# mcu_v042.net
KiCad netlist of a schematic drawn in EAGLE
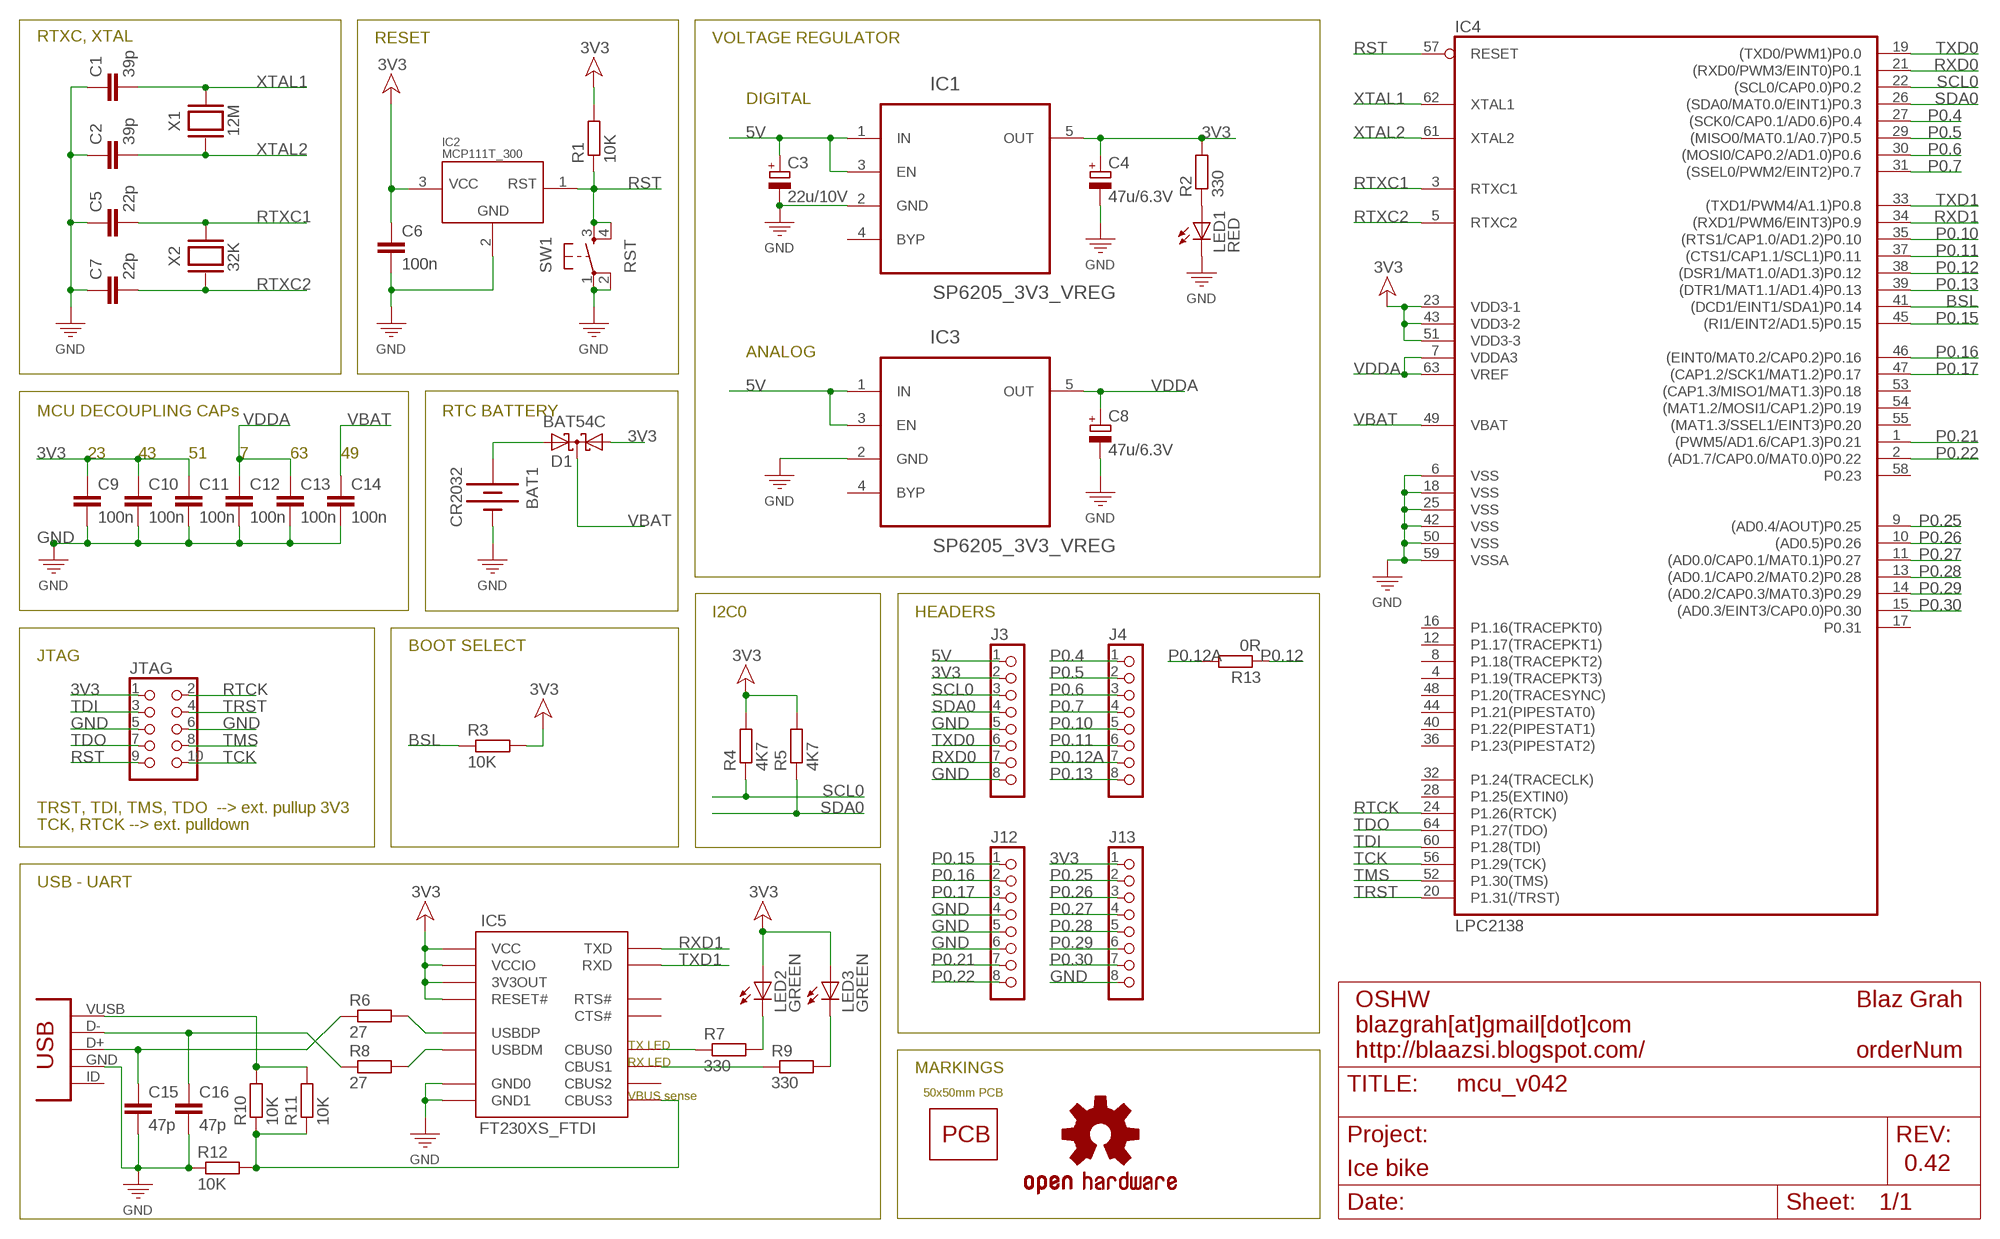
[diagram p0: schematic, sheet 1]

(export (version "E")
  (design (tool "Eeschema 10.0.6"))
  (components
    (comp (ref "BAT1")
      (value "CR2032")
      (footprint "eagle-import:BATTERY_20MM_SMD")
      (libsource (lib "eagle-import") (part "BATTERY20MM"))
    )
    (comp (ref "C1")
      (value "39p")
      (footprint "eagle-import:C0603")
      (libsource (lib "eagle-import") (part "C-EUC0603"))
    )
    (comp (ref "C2")
      (value "39p")
      (footprint "eagle-import:C0603")
      (libsource (lib "eagle-import") (part "C-EUC0603"))
    )
    (comp (ref "C3")
      (value "22u/10V")
      (footprint "eagle-import:SMC_B")
      (libsource (lib "eagle-import") (part "CAPACITOR_POL-SMC_B"))
    )
    (comp (ref "C4")
      (value "47u/6.3V")
      (footprint "eagle-import:SMC_B")
      (libsource (lib "eagle-import") (part "CAPACITOR_POL-SMC_B"))
    )
    (comp (ref "C5")
      (value "22p")
      (footprint "eagle-import:C0603")
      (libsource (lib "eagle-import") (part "C-EUC0603"))
    )
    (comp (ref "C6")
      (value "100n")
      (footprint "eagle-import:C0603")
      (libsource (lib "eagle-import") (part "C-EUC0603"))
    )
    (comp (ref "C7")
      (value "22p")
      (footprint "eagle-import:C0603")
      (libsource (lib "eagle-import") (part "C-EUC0603"))
    )
    (comp (ref "C8")
      (value "47u/6.3V")
      (footprint "eagle-import:SMC_B")
      (libsource (lib "eagle-import") (part "CAPACITOR_POL-SMC_B"))
    )
    (comp (ref "C9")
      (value "100n")
      (footprint "eagle-import:C0603")
      (libsource (lib "eagle-import") (part "C-EUC0603"))
    )
    (comp (ref "C10")
      (value "100n")
      (footprint "eagle-import:C0603")
      (libsource (lib "eagle-import") (part "C-EUC0603"))
    )
    (comp (ref "C11")
      (value "100n")
      (footprint "eagle-import:C0603")
      (libsource (lib "eagle-import") (part "C-EUC0603"))
    )
    (comp (ref "C12")
      (value "100n")
      (footprint "eagle-import:C0603")
      (libsource (lib "eagle-import") (part "C-EUC0603"))
    )
    (comp (ref "C13")
      (value "100n")
      (footprint "eagle-import:C0603")
      (libsource (lib "eagle-import") (part "C-EUC0603"))
    )
    (comp (ref "C14")
      (value "100n")
      (footprint "eagle-import:C0603")
      (libsource (lib "eagle-import") (part "C-EUC0603"))
    )
    (comp (ref "C15")
      (value "47p")
      (footprint "eagle-import:C0603")
      (libsource (lib "eagle-import") (part "C-EUC0603"))
    )
    (comp (ref "C16")
      (value "47p")
      (footprint "eagle-import:C0603")
      (libsource (lib "eagle-import") (part "C-EUC0603"))
    )
    (comp (ref "D1")
      (value "BAT54C")
      (footprint "eagle-import:SOT23")
      (libsource (lib "eagle-import") (part "BAT54C"))
    )
    (comp (ref "DOC")
      (value "FRAME_DINA4_L")
      (footprint "eagle-import:DP_LOGO")
      (fields
        (field (name "AUTHOR") "Blaz Grah")
        (field (name "LICENSE") "OSHW")
        (field (name "PROJECT") "Ice bike")
        (field (name "REV") "0.42")
        (field (name "URL1") "blazgrah[at]gmail[dot]com")
        (field (name "URL2") "http://blaazsi.blogspot.com/")
      )
      (libsource (lib "eagle-import") (part "FRAME_DINA4_L"))
    )
    (comp (ref "IC1")
      (value "SP6205_3V3_VREG")
      (footprint "eagle-import:SOT23-5")
      (libsource (lib "eagle-import") (part "SP6205_3V3_VREG"))
    )
    (comp (ref "IC2")
      (value "MCP111T_300")
      (footprint "eagle-import:SOT23")
      (libsource (lib "eagle-import") (part "MCP111T_300"))
    )
    (comp (ref "IC3")
      (value "SP6205_3V3_VREG")
      (footprint "eagle-import:SOT23-5")
      (libsource (lib "eagle-import") (part "SP6205_3V3_VREG"))
    )
    (comp (ref "IC4")
      (value "LPC2138")
      (footprint "eagle-import:LQFP64")
      (libsource (lib "eagle-import") (part "LCP2138_LQFP64"))
    )
    (comp (ref "IC5")
      (value "FT230XS_FTDI")
      (footprint "eagle-import:SSOP16")
      (libsource (lib "eagle-import") (part "FT230XS_FTDI"))
    )
    (comp (ref "J3")
      (value "CON_HEADER_1X08-PTH")
      (footprint "eagle-import:M1X8")
      (libsource (lib "eagle-import") (part "CON_HEADER_1X08-PTH"))
    )
    (comp (ref "J4")
      (value "CON_HEADER_1X08-PTH")
      (footprint "eagle-import:M1X8")
      (libsource (lib "eagle-import") (part "CON_HEADER_1X08-PTH"))
    )
    (comp (ref "J12")
      (value "CON_HEADER_1X08-PTH")
      (footprint "eagle-import:M1X8")
      (libsource (lib "eagle-import") (part "CON_HEADER_1X08-PTH"))
    )
    (comp (ref "J13")
      (value "CON_HEADER_1X08-PTH")
      (footprint "eagle-import:M1X8")
      (libsource (lib "eagle-import") (part "CON_HEADER_1X08-PTH"))
    )
    (comp (ref "JTAG")
      (value "CON_HEADER_2X05-PTH+SHROUDED_A")
      (footprint "eagle-import:PINSHRD_PTH_2X05")
      (libsource (lib "eagle-import") (part "CON_HEADER_2X05-PTH+SHROUDED_A"))
    )
    (comp (ref "LED1")
      (value "RED")
      (footprint "eagle-import:LED0805")
      (libsource (lib "eagle-import") (part "LED0805"))
    )
    (comp (ref "LED2")
      (value "GREEN")
      (footprint "eagle-import:LED0805")
      (libsource (lib "eagle-import") (part "LED0805"))
    )
    (comp (ref "LED3")
      (value "GREEN")
      (footprint "eagle-import:LED0805")
      (libsource (lib "eagle-import") (part "LED0805"))
    )
    (comp (ref "LOGO1")
      (value "OSHW-LOGOS")
      (footprint "eagle-import:OSHW-LOGO-S")
      (libsource (lib "eagle-import") (part "OSHW-LOGOS"))
    )
    (comp (ref "PCB1")
      (value "PCB")
      (footprint "eagle-import:PCB_50X50")
      (libsource (lib "eagle-import") (part "PCB"))
    )
    (comp (ref "R1")
      (value "10K")
      (footprint "eagle-import:R0603")
      (libsource (lib "eagle-import") (part "R-EU0603"))
    )
    (comp (ref "R2")
      (value "330")
      (footprint "eagle-import:R0603")
      (libsource (lib "eagle-import") (part "R-EU0603"))
    )
    (comp (ref "R3")
      (value "10K")
      (footprint "eagle-import:R0603")
      (libsource (lib "eagle-import") (part "R-EU0603"))
    )
    (comp (ref "R4")
      (value "4K7")
      (footprint "eagle-import:R0603")
      (libsource (lib "eagle-import") (part "R-EU0603"))
    )
    (comp (ref "R5")
      (value "4K7")
      (footprint "eagle-import:R0603")
      (libsource (lib "eagle-import") (part "R-EU0603"))
    )
    (comp (ref "R6")
      (value "27")
      (footprint "eagle-import:R0603")
      (libsource (lib "eagle-import") (part "R-EU0603"))
    )
    (comp (ref "R7")
      (value "330")
      (footprint "eagle-import:R0603")
      (libsource (lib "eagle-import") (part "R-EU0603"))
    )
    (comp (ref "R8")
      (value "27")
      (footprint "eagle-import:R0603")
      (libsource (lib "eagle-import") (part "R-EU0603"))
    )
    (comp (ref "R9")
      (value "330")
      (footprint "eagle-import:R0603")
      (libsource (lib "eagle-import") (part "R-EU0603"))
    )
    (comp (ref "R10")
      (value "10K")
      (footprint "eagle-import:R0603")
      (libsource (lib "eagle-import") (part "R-EU0603"))
    )
    (comp (ref "R11")
      (value "10K")
      (footprint "eagle-import:R0603")
      (libsource (lib "eagle-import") (part "R-EU0603"))
    )
    (comp (ref "R12")
      (value "10K")
      (footprint "eagle-import:R0603")
      (libsource (lib "eagle-import") (part "R-EU0603"))
    )
    (comp (ref "R13")
      (value "0R")
      (footprint "eagle-import:R0603")
      (libsource (lib "eagle-import") (part "R-EU0603"))
    )
    (comp (ref "SW1")
      (value "RST")
      (footprint "eagle-import:BUTTON_SW_4P_SMD")
      (libsource (lib "eagle-import") (part "TACTIL_BUTTON"))
    )
    (comp (ref "USB1")
      (value "CON-USB-F-MINI-B")
      (footprint "eagle-import:CONN_USB_MINI-B")
      (libsource (lib "eagle-import") (part "CON-USB-F-MINI-B"))
    )
    (comp (ref "X1")
      (value "12M")
      (footprint "eagle-import:CRYSTAL_12M_4.8X10.6MM")
      (libsource (lib "eagle-import") (part "CRYSTALSMD_4.8X10.6"))
    )
    (comp (ref "X2")
      (value "32K")
      (footprint "eagle-import:CRYSTAL_32K_SMD")
      (libsource (lib "eagle-import") (part "CRYSTALSMD_32K"))
    )
  )
  (nets
    (net (code "1") (name "/5V") (class "Default")
      (node (ref "C3") (pin "+") (pinfunction "+_+") (pintype "passive"))
      (node (ref "IC1") (pin "1") (pinfunction "IN_1") (pintype "input"))
      (node (ref "IC1") (pin "3") (pinfunction "EN_3") (pintype "input"))
      (node (ref "IC3") (pin "1") (pinfunction "IN_1") (pintype "input"))
      (node (ref "IC3") (pin "3") (pinfunction "EN_3") (pintype "input"))
      (node (ref "J3") (pin "1") (pinfunction "1_1") (pintype "passive"))
    )
    (net (code "2") (name "/BSL") (class "Default")
      (node (ref "IC4") (pin "41") (pinfunction "(DCD1/EINT1/SDA1)P0.14_41") (pintype "bidirectional"))
      (node (ref "R3") (pin "1") (pinfunction "1_1") (pintype "passive"))
    )
    (net (code "3") (name "/P0.4") (class "Default")
      (node (ref "IC4") (pin "27") (pinfunction "(SCK0/CAP0.1/AD0.6)P0.4_27") (pintype "bidirectional"))
      (node (ref "J4") (pin "1") (pinfunction "1_1") (pintype "passive"))
    )
    (net (code "4") (name "/P0.5") (class "Default")
      (node (ref "IC4") (pin "29") (pinfunction "(MISO0/MAT0.1/A0.7)P0.5_29") (pintype "bidirectional"))
      (node (ref "J4") (pin "2") (pinfunction "2_2") (pintype "passive"))
    )
    (net (code "5") (name "/P0.6") (class "Default")
      (node (ref "IC4") (pin "30") (pinfunction "(MOSI0/CAP0.2/AD1.0)P0.6_30") (pintype "bidirectional"))
      (node (ref "J4") (pin "3") (pinfunction "3_3") (pintype "passive"))
    )
    (net (code "6") (name "/P0.7") (class "Default")
      (node (ref "IC4") (pin "31") (pinfunction "(SSEL0/PWM2/EINT2)P0.7_31") (pintype "bidirectional"))
      (node (ref "J4") (pin "4") (pinfunction "4_4") (pintype "passive"))
    )
    (net (code "7") (name "/P0.10") (class "Default")
      (node (ref "IC4") (pin "35") (pinfunction "(RTS1/CAP1.0/AD1.2)P0.10_35") (pintype "bidirectional"))
      (node (ref "J4") (pin "5") (pinfunction "5_5") (pintype "passive"))
    )
    (net (code "8") (name "/P0.11") (class "Default")
      (node (ref "IC4") (pin "37") (pinfunction "(CTS1/CAP1.1/SCL1)P0.11_37") (pintype "bidirectional"))
      (node (ref "J4") (pin "6") (pinfunction "6_6") (pintype "passive"))
    )
    (net (code "9") (name "/P0.12") (class "Default")
      (node (ref "IC4") (pin "38") (pinfunction "(DSR1/MAT1.0/AD1.3)P0.12_38") (pintype "bidirectional"))
      (node (ref "R13") (pin "1") (pinfunction "1_1") (pintype "passive"))
    )
    (net (code "10") (name "/P0.12A") (class "Default")
      (node (ref "J4") (pin "7") (pinfunction "7_7") (pintype "passive"))
      (node (ref "R13") (pin "2") (pinfunction "2_2") (pintype "passive"))
    )
    (net (code "11") (name "/P0.13") (class "Default")
      (node (ref "IC4") (pin "39") (pinfunction "(DTR1/MAT1.1/AD1.4)P0.13_39") (pintype "bidirectional"))
      (node (ref "J4") (pin "8") (pinfunction "8_8") (pintype "passive"))
    )
    (net (code "12") (name "/P0.15") (class "Default")
      (node (ref "IC4") (pin "45") (pinfunction "(RI1/EINT2/AD1.5)P0.15_45") (pintype "bidirectional"))
      (node (ref "J12") (pin "1") (pinfunction "1_1") (pintype "passive"))
    )
    (net (code "13") (name "/P0.16") (class "Default")
      (node (ref "IC4") (pin "46") (pinfunction "(EINT0/MAT0.2/CAP0.2)P0.16_46") (pintype "bidirectional"))
      (node (ref "J12") (pin "2") (pinfunction "2_2") (pintype "passive"))
    )
    (net (code "14") (name "/P0.17") (class "Default")
      (node (ref "IC4") (pin "47") (pinfunction "(CAP1.2/SCK1/MAT1.2)P0.17_47") (pintype "bidirectional"))
      (node (ref "J12") (pin "3") (pinfunction "3_3") (pintype "passive"))
    )
    (net (code "15") (name "/P0.21") (class "Default")
      (node (ref "IC4") (pin "1") (pinfunction "(PWM5/AD1.6/CAP1.3)P0.21_1") (pintype "bidirectional"))
      (node (ref "J12") (pin "7") (pinfunction "7_7") (pintype "passive"))
    )
    (net (code "16") (name "/P0.22") (class "Default")
      (node (ref "IC4") (pin "2") (pinfunction "(AD1.7/CAP0.0/MAT0.0)P0.22_2") (pintype "bidirectional"))
      (node (ref "J12") (pin "8") (pinfunction "8_8") (pintype "passive"))
    )
    (net (code "17") (name "/P0.25") (class "Default")
      (node (ref "IC4") (pin "9") (pinfunction "(AD0.4/AOUT)P0.25_9") (pintype "bidirectional"))
      (node (ref "J13") (pin "2") (pinfunction "2_2") (pintype "passive"))
    )
    (net (code "18") (name "/P0.26") (class "Default")
      (node (ref "IC4") (pin "10") (pinfunction "(AD0.5)P0.26_10") (pintype "bidirectional"))
      (node (ref "J13") (pin "3") (pinfunction "3_3") (pintype "passive"))
    )
    (net (code "19") (name "/P0.27") (class "Default")
      (node (ref "IC4") (pin "11") (pinfunction "(AD0.0/CAP0.1/MAT0.1)P0.27_11") (pintype "bidirectional"))
      (node (ref "J13") (pin "4") (pinfunction "4_4") (pintype "passive"))
    )
    (net (code "20") (name "/P0.28") (class "Default")
      (node (ref "IC4") (pin "13") (pinfunction "(AD0.1/CAP0.2/MAT0.2)P0.28_13") (pintype "bidirectional"))
      (node (ref "J13") (pin "5") (pinfunction "5_5") (pintype "passive"))
    )
    (net (code "21") (name "/P0.29") (class "Default")
      (node (ref "IC4") (pin "14") (pinfunction "(AD0.2/CAP0.3/MAT0.3)P0.29_14") (pintype "bidirectional"))
      (node (ref "J13") (pin "6") (pinfunction "6_6") (pintype "passive"))
    )
    (net (code "22") (name "/P0.30") (class "Default")
      (node (ref "IC4") (pin "15") (pinfunction "(AD0.3/EINT3/CAP0.0)P0.30_15") (pintype "bidirectional"))
      (node (ref "J13") (pin "7") (pinfunction "7_7") (pintype "passive"))
    )
    (net (code "23") (name "/RST") (class "Default")
      (node (ref "IC2") (pin "1") (pinfunction "RST_1") (pintype "output"))
      (node (ref "IC4") (pin "57") (pinfunction "RESET_57") (pintype "input"))
      (node (ref "JTAG") (pin "9") (pinfunction "9_9") (pintype "passive"))
      (node (ref "R1") (pin "1") (pinfunction "1_1") (pintype "passive"))
      (node (ref "SW1") (pin "3") (pinfunction "3_3") (pintype "passive"))
      (node (ref "SW1") (pin "4") (pinfunction "4_4") (pintype "passive"))
    )
    (net (code "24") (name "/RTCK") (class "Default")
      (node (ref "IC4") (pin "24") (pinfunction "P1.26(RTCK)_24") (pintype "bidirectional"))
      (node (ref "JTAG") (pin "2") (pinfunction "2_2") (pintype "passive"))
    )
    (net (code "25") (name "/RTXC1") (class "Default")
      (node (ref "C5") (pin "2") (pinfunction "2_2") (pintype "passive"))
      (node (ref "IC4") (pin "3") (pinfunction "RTXC1_3") (pintype "input"))
      (node (ref "X2") (pin "X2") (pinfunction "2_X2") (pintype "passive"))
    )
    (net (code "26") (name "/RTXC2") (class "Default")
      (node (ref "C7") (pin "2") (pinfunction "2_2") (pintype "passive"))
      (node (ref "IC4") (pin "5") (pinfunction "RTXC2_5") (pintype "output"))
      (node (ref "X2") (pin "X1") (pinfunction "1_X1") (pintype "passive"))
    )
    (net (code "27") (name "/RXD0") (class "Default")
      (node (ref "IC4") (pin "21") (pinfunction "(RXD0/PWM3/EINT0)P0.1_21") (pintype "bidirectional"))
      (node (ref "J3") (pin "7") (pinfunction "7_7") (pintype "passive"))
    )
    (net (code "28") (name "/RXD1") (class "Default")
      (node (ref "IC4") (pin "34") (pinfunction "(RXD1/PWM6/EINT3)P0.9_34") (pintype "bidirectional"))
      (node (ref "IC5") (pin "P$1") (pinfunction "TXD_P$1") (pintype "bidirectional"))
    )
    (net (code "29") (name "/SCL0") (class "Default")
      (node (ref "IC4") (pin "22") (pinfunction "(SCL0/CAP0.0)P0.2_22") (pintype "bidirectional"))
      (node (ref "J3") (pin "3") (pinfunction "3_3") (pintype "passive"))
      (node (ref "R4") (pin "1") (pinfunction "1_1") (pintype "passive"))
    )
    (net (code "30") (name "/SDA0") (class "Default")
      (node (ref "IC4") (pin "26") (pinfunction "(SDA0/MAT0.0/EINT1)P0.3_26") (pintype "bidirectional"))
      (node (ref "J3") (pin "4") (pinfunction "4_4") (pintype "passive"))
      (node (ref "R5") (pin "1") (pinfunction "1_1") (pintype "passive"))
    )
    (net (code "31") (name "/TCK") (class "Default")
      (node (ref "IC4") (pin "56") (pinfunction "P1.29(TCK)_56") (pintype "bidirectional"))
      (node (ref "JTAG") (pin "10") (pinfunction "10_10") (pintype "passive"))
    )
    (net (code "32") (name "/TDI") (class "Default")
      (node (ref "IC4") (pin "60") (pinfunction "P1.28(TDI)_60") (pintype "bidirectional"))
      (node (ref "JTAG") (pin "3") (pinfunction "3_3") (pintype "passive"))
    )
    (net (code "33") (name "/TDO") (class "Default")
      (node (ref "IC4") (pin "64") (pinfunction "P1.27(TDO)_64") (pintype "bidirectional"))
      (node (ref "JTAG") (pin "7") (pinfunction "7_7") (pintype "passive"))
    )
    (net (code "34") (name "/TMS") (class "Default")
      (node (ref "IC4") (pin "52") (pinfunction "P1.30(TMS)_52") (pintype "bidirectional"))
      (node (ref "JTAG") (pin "8") (pinfunction "8_8") (pintype "passive"))
    )
    (net (code "35") (name "/TRST") (class "Default")
      (node (ref "IC4") (pin "20") (pinfunction "P1.31(/TRST)_20") (pintype "bidirectional"))
      (node (ref "JTAG") (pin "4") (pinfunction "4_4") (pintype "passive"))
    )
    (net (code "36") (name "/TXD0") (class "Default")
      (node (ref "IC4") (pin "19") (pinfunction "(TXD0/PWM1)P0.0_19") (pintype "bidirectional"))
      (node (ref "J3") (pin "6") (pinfunction "6_6") (pintype "passive"))
    )
    (net (code "37") (name "/TXD1") (class "Default")
      (node (ref "IC4") (pin "33") (pinfunction "(TXD1/PWM4/A1.1)P0.8_33") (pintype "bidirectional"))
      (node (ref "IC5") (pin "P$4") (pinfunction "RXD_P$4") (pintype "bidirectional"))
    )
    (net (code "38") (name "/VBAT") (class "Default")
      (node (ref "C14") (pin "1") (pinfunction "1_1") (pintype "passive"))
      (node (ref "D1") (pin "3") (pinfunction "CC_3") (pintype "passive"))
      (node (ref "IC4") (pin "49") (pinfunction "VBAT_49") (pintype "power_in"))
    )
    (net (code "39") (name "/VDDA") (class "Default")
      (node (ref "C12") (pin "1") (pinfunction "1_1") (pintype "passive"))
      (node (ref "C13") (pin "1") (pinfunction "1_1") (pintype "passive"))
      (node (ref "C8") (pin "+") (pinfunction "+_+") (pintype "passive"))
      (node (ref "IC3") (pin "5") (pinfunction "OUT_5") (pintype "power_in"))
      (node (ref "IC4") (pin "63") (pinfunction "VREF_63") (pintype "input"))
      (node (ref "IC4") (pin "7") (pinfunction "VDDA3_7") (pintype "power_in"))
    )
    (net (code "40") (name "/XTAL1") (class "Default")
      (node (ref "C1") (pin "2") (pinfunction "2_2") (pintype "passive"))
      (node (ref "IC4") (pin "62") (pinfunction "XTAL1_62") (pintype "input"))
      (node (ref "X1") (pin "P$2") (pinfunction "2_P$2") (pintype "passive"))
    )
    (net (code "41") (name "/XTAL2") (class "Default")
      (node (ref "C2") (pin "2") (pinfunction "2_2") (pintype "passive"))
      (node (ref "IC4") (pin "61") (pinfunction "XTAL2_61") (pintype "output"))
      (node (ref "X1") (pin "P$1") (pinfunction "1_P$1") (pintype "passive"))
    )
    (net (code "42") (name "3V3") (class "Default")
      (node (ref "C10") (pin "1") (pinfunction "1_1") (pintype "passive"))
      (node (ref "C11") (pin "1") (pinfunction "1_1") (pintype "passive"))
      (node (ref "C4") (pin "+") (pinfunction "+_+") (pintype "passive"))
      (node (ref "C6") (pin "1") (pinfunction "1_1") (pintype "passive"))
      (node (ref "C9") (pin "1") (pinfunction "1_1") (pintype "passive"))
      (node (ref "D1") (pin "1") (pinfunction "A1_1") (pintype "passive"))
      (node (ref "IC1") (pin "5") (pinfunction "OUT_5") (pintype "power_in"))
      (node (ref "IC2") (pin "3") (pinfunction "VCC_3") (pintype "input"))
      (node (ref "IC4") (pin "23") (pinfunction "VDD3-1_23") (pintype "power_in"))
      (node (ref "IC4") (pin "43") (pinfunction "VDD3-2_43") (pintype "power_in"))
      (node (ref "IC4") (pin "51") (pinfunction "VDD3-3_51") (pintype "power_in"))
      (node (ref "IC5") (pin "P$10") (pinfunction "3V3OUT_P$10") (pintype "power_in"))
      (node (ref "IC5") (pin "P$11") (pinfunction "RESET#_P$11") (pintype "bidirectional"))
      (node (ref "IC5") (pin "P$12") (pinfunction "VCC_P$12") (pintype "power_in"))
      (node (ref "IC5") (pin "P$3") (pinfunction "VCCIO_P$3") (pintype "power_in"))
      (node (ref "J13") (pin "1") (pinfunction "1_1") (pintype "passive"))
      (node (ref "J3") (pin "2") (pinfunction "2_2") (pintype "passive"))
      (node (ref "JTAG") (pin "1") (pinfunction "1_1") (pintype "passive"))
      (node (ref "LED2") (pin "A") (pinfunction "A_A") (pintype "passive"))
      (node (ref "LED3") (pin "A") (pinfunction "A_A") (pintype "passive"))
      (node (ref "R1") (pin "2") (pinfunction "2_2") (pintype "passive"))
      (node (ref "R2") (pin "2") (pinfunction "2_2") (pintype "passive"))
      (node (ref "R3") (pin "2") (pinfunction "2_2") (pintype "passive"))
      (node (ref "R4") (pin "2") (pinfunction "2_2") (pintype "passive"))
      (node (ref "R5") (pin "2") (pinfunction "2_2") (pintype "passive"))
    )
    (net (code "43") (name "GND") (class "Default")
      (node (ref "BAT1") (pin "NEG") (pinfunction "NEG_NEG") (pintype "power_in"))
      (node (ref "C1") (pin "1") (pinfunction "1_1") (pintype "passive"))
      (node (ref "C10") (pin "2") (pinfunction "2_2") (pintype "passive"))
      (node (ref "C11") (pin "2") (pinfunction "2_2") (pintype "passive"))
      (node (ref "C12") (pin "2") (pinfunction "2_2") (pintype "passive"))
      (node (ref "C13") (pin "2") (pinfunction "2_2") (pintype "passive"))
      (node (ref "C14") (pin "2") (pinfunction "2_2") (pintype "passive"))
      (node (ref "C15") (pin "2") (pinfunction "2_2") (pintype "passive"))
      (node (ref "C16") (pin "2") (pinfunction "2_2") (pintype "passive"))
      (node (ref "C2") (pin "1") (pinfunction "1_1") (pintype "passive"))
      (node (ref "C3") (pin "-") (pinfunction "-_-") (pintype "passive"))
      (node (ref "C4") (pin "-") (pinfunction "-_-") (pintype "passive"))
      (node (ref "C5") (pin "1") (pinfunction "1_1") (pintype "passive"))
      (node (ref "C6") (pin "2") (pinfunction "2_2") (pintype "passive"))
      (node (ref "C7") (pin "1") (pinfunction "1_1") (pintype "passive"))
      (node (ref "C8") (pin "-") (pinfunction "-_-") (pintype "passive"))
      (node (ref "C9") (pin "2") (pinfunction "2_2") (pintype "passive"))
      (node (ref "IC1") (pin "2") (pinfunction "GND_2") (pintype "power_in"))
      (node (ref "IC2") (pin "2") (pinfunction "GND_2") (pintype "power_in"))
      (node (ref "IC3") (pin "2") (pinfunction "GND_2") (pintype "power_in"))
      (node (ref "IC4") (pin "18") (pinfunction "VSS_18") (pintype "power_in"))
      (node (ref "IC4") (pin "25") (pinfunction "VSS_25") (pintype "power_in"))
      (node (ref "IC4") (pin "42") (pinfunction "VSS_42") (pintype "power_in"))
      (node (ref "IC4") (pin "50") (pinfunction "VSS_50") (pintype "power_in"))
      (node (ref "IC4") (pin "59") (pinfunction "VSSA_59") (pintype "power_in"))
      (node (ref "IC4") (pin "6") (pinfunction "VSS_6") (pintype "power_in"))
      (node (ref "IC5") (pin "P$13") (pinfunction "GND1_P$13") (pintype "power_in"))
      (node (ref "IC5") (pin "P$5") (pinfunction "GND0_P$5") (pintype "power_in"))
      (node (ref "J12") (pin "4") (pinfunction "4_4") (pintype "passive"))
      (node (ref "J12") (pin "5") (pinfunction "5_5") (pintype "passive"))
      (node (ref "J12") (pin "6") (pinfunction "6_6") (pintype "passive"))
      (node (ref "J13") (pin "8") (pinfunction "8_8") (pintype "passive"))
      (node (ref "J3") (pin "5") (pinfunction "5_5") (pintype "passive"))
      (node (ref "J3") (pin "8") (pinfunction "8_8") (pintype "passive"))
      (node (ref "JTAG") (pin "5") (pinfunction "5_5") (pintype "passive"))
      (node (ref "JTAG") (pin "6") (pinfunction "6_6") (pintype "passive"))
      (node (ref "LED1") (pin "C") (pinfunction "C_C") (pintype "passive"))
      (node (ref "R12") (pin "1") (pinfunction "1_1") (pintype "passive"))
      (node (ref "SW1") (pin "1") (pinfunction "1_1") (pintype "passive"))
      (node (ref "SW1") (pin "2") (pinfunction "2_2") (pintype "passive"))
      (node (ref "USB1") (pin "GND") (pinfunction "GND_GND") (pintype "bidirectional"))
    )
    (net (code "44") (name "Net-(C15-Pad1)") (class "Default")
      (node (ref "C15") (pin "1") (pinfunction "1_1") (pintype "passive"))
      (node (ref "R6") (pin "1") (pinfunction "1_1") (pintype "passive"))
      (node (ref "USB1") (pin "D+") (pinfunction "D+_D+") (pintype "bidirectional"))
    )
    (net (code "45") (name "Net-(C16-Pad1)") (class "Default")
      (node (ref "C16") (pin "1") (pinfunction "1_1") (pintype "passive"))
      (node (ref "R8") (pin "1") (pinfunction "1_1") (pintype "passive"))
      (node (ref "USB1") (pin "D-") (pinfunction "D-_D-") (pintype "bidirectional"))
    )
    (net (code "46") (name "Net-(D1-A2)") (class "Default")
      (node (ref "BAT1") (pin "POS1") (pinfunction "POZ_POS1") (pintype "power_in"))
      (node (ref "BAT1") (pin "POS2") (pinfunction "POZ_POS2") (pintype "power_in"))
      (node (ref "D1") (pin "2") (pinfunction "A2_2") (pintype "passive"))
    )
    (net (code "47") (name "Net-(IC5-CBUS0)") (class "Default")
      (node (ref "IC5") (pin "P$15") (pinfunction "CBUS0_P$15") (pintype "bidirectional"))
      (node (ref "R7") (pin "1") (pinfunction "1_1") (pintype "passive"))
    )
    (net (code "48") (name "Net-(IC5-CBUS1)") (class "Default")
      (node (ref "IC5") (pin "P$14") (pinfunction "CBUS1_P$14") (pintype "bidirectional"))
      (node (ref "R9") (pin "1") (pinfunction "1_1") (pintype "passive"))
    )
    (net (code "49") (name "Net-(IC5-CBUS3)") (class "Default")
      (node (ref "IC5") (pin "P$16") (pinfunction "CBUS3_P$16") (pintype "bidirectional"))
      (node (ref "R10") (pin "1") (pinfunction "1_1") (pintype "passive"))
      (node (ref "R11") (pin "1") (pinfunction "1_1") (pintype "passive"))
      (node (ref "R12") (pin "2") (pinfunction "2_2") (pintype "passive"))
    )
    (net (code "50") (name "Net-(IC5-USBDM)") (class "Default")
      (node (ref "IC5") (pin "P$9") (pinfunction "USBDM_P$9") (pintype "bidirectional"))
      (node (ref "R8") (pin "2") (pinfunction "2_2") (pintype "passive"))
    )
    (net (code "51") (name "Net-(IC5-USBDP)") (class "Default")
      (node (ref "IC5") (pin "P$8") (pinfunction "USBDP_P$8") (pintype "bidirectional"))
      (node (ref "R6") (pin "2") (pinfunction "2_2") (pintype "passive"))
    )
    (net (code "52") (name "Net-(LED1-PadA)") (class "Default")
      (node (ref "LED1") (pin "A") (pinfunction "A_A") (pintype "passive"))
      (node (ref "R2") (pin "1") (pinfunction "1_1") (pintype "passive"))
    )
    (net (code "53") (name "Net-(LED2-PadC)") (class "Default")
      (node (ref "LED2") (pin "C") (pinfunction "C_C") (pintype "passive"))
      (node (ref "R7") (pin "2") (pinfunction "2_2") (pintype "passive"))
    )
    (net (code "54") (name "Net-(LED3-PadC)") (class "Default")
      (node (ref "LED3") (pin "C") (pinfunction "C_C") (pintype "passive"))
      (node (ref "R9") (pin "2") (pinfunction "2_2") (pintype "passive"))
    )
    (net (code "55") (name "Net-(R10-Pad2)") (class "Default")
      (node (ref "R10") (pin "2") (pinfunction "2_2") (pintype "passive"))
      (node (ref "R11") (pin "2") (pinfunction "2_2") (pintype "passive"))
      (node (ref "USB1") (pin "VUSB") (pinfunction "VUSB_VUSB") (pintype "bidirectional"))
    )
    (net (code "56") (name "unconnected-(IC1-BYP-Pad4)") (class "Default")
      (node (ref "IC1") (pin "4") (pinfunction "BYP_4") (pintype "no_connect"))
    )
    (net (code "57") (name "unconnected-(IC3-BYP-Pad4)") (class "Default")
      (node (ref "IC3") (pin "4") (pinfunction "BYP_4") (pintype "no_connect"))
    )
    (net (code "58") (name "unconnected-(IC4-(CAP1.3{slash}MISO1{slash}MAT1.3)P0.18-Pad53)") (class "Default")
      (node (ref "IC4") (pin "53") (pinfunction "(CAP1.3/MISO1/MAT1.3)P0.18_53") (pintype "bidirectional"))
    )
    (net (code "59") (name "unconnected-(IC4-(MAT1.2{slash}MOSI1{slash}CAP1.2)P0.19-Pad54)") (class "Default")
      (node (ref "IC4") (pin "54") (pinfunction "(MAT1.2/MOSI1/CAP1.2)P0.19_54") (pintype "bidirectional"))
    )
    (net (code "60") (name "unconnected-(IC4-(MAT1.3{slash}SSEL1{slash}EINT3)P0.20-Pad55)") (class "Default")
      (node (ref "IC4") (pin "55") (pinfunction "(MAT1.3/SSEL1/EINT3)P0.20_55") (pintype "bidirectional"))
    )
    (net (code "61") (name "unconnected-(IC4-P0.23-Pad58)") (class "Default")
      (node (ref "IC4") (pin "58") (pinfunction "P0.23_58") (pintype "bidirectional"))
    )
    (net (code "62") (name "unconnected-(IC4-P0.31-Pad17)") (class "Default")
      (node (ref "IC4") (pin "17") (pinfunction "P0.31_17") (pintype "output"))
    )
    (net (code "63") (name "unconnected-(IC4-P1.16(TRACEPKT0)-Pad16)") (class "Default")
      (node (ref "IC4") (pin "16") (pinfunction "P1.16(TRACEPKT0)_16") (pintype "bidirectional"))
    )
    (net (code "64") (name "unconnected-(IC4-P1.17(TRACEPKT1)-Pad12)") (class "Default")
      (node (ref "IC4") (pin "12") (pinfunction "P1.17(TRACEPKT1)_12") (pintype "bidirectional"))
    )
    (net (code "65") (name "unconnected-(IC4-P1.18(TRACEPKT2)-Pad8)") (class "Default")
      (node (ref "IC4") (pin "8") (pinfunction "P1.18(TRACEPKT2)_8") (pintype "bidirectional"))
    )
    (net (code "66") (name "unconnected-(IC4-P1.19(TRACEPKT3)-Pad4)") (class "Default")
      (node (ref "IC4") (pin "4") (pinfunction "P1.19(TRACEPKT3)_4") (pintype "bidirectional"))
    )
    (net (code "67") (name "unconnected-(IC4-P1.20(TRACESYNC)-Pad48)") (class "Default")
      (node (ref "IC4") (pin "48") (pinfunction "P1.20(TRACESYNC)_48") (pintype "bidirectional"))
    )
    (net (code "68") (name "unconnected-(IC4-P1.21(PIPESTAT0)-Pad44)") (class "Default")
      (node (ref "IC4") (pin "44") (pinfunction "P1.21(PIPESTAT0)_44") (pintype "bidirectional"))
    )
    (net (code "69") (name "unconnected-(IC4-P1.22(PIPESTAT1)-Pad40)") (class "Default")
      (node (ref "IC4") (pin "40") (pinfunction "P1.22(PIPESTAT1)_40") (pintype "bidirectional"))
    )
    (net (code "70") (name "unconnected-(IC4-P1.23(PIPESTAT2)-Pad36)") (class "Default")
      (node (ref "IC4") (pin "36") (pinfunction "P1.23(PIPESTAT2)_36") (pintype "bidirectional"))
    )
    (net (code "71") (name "unconnected-(IC4-P1.24(TRACECLK)-Pad32)") (class "Default")
      (node (ref "IC4") (pin "32") (pinfunction "P1.24(TRACECLK)_32") (pintype "bidirectional"))
    )
    (net (code "72") (name "unconnected-(IC4-P1.25(EXTIN0)-Pad28)") (class "Default")
      (node (ref "IC4") (pin "28") (pinfunction "P1.25(EXTIN0)_28") (pintype "bidirectional"))
    )
    (net (code "73") (name "unconnected-(IC5-CBUS2-PadP$7)") (class "Default")
      (node (ref "IC5") (pin "P$7") (pinfunction "CBUS2_P$7") (pintype "bidirectional"))
    )
    (net (code "74") (name "unconnected-(IC5-CTS#-PadP$6)") (class "Default")
      (node (ref "IC5") (pin "P$6") (pinfunction "CTS#_P$6") (pintype "bidirectional"))
    )
    (net (code "75") (name "unconnected-(IC5-RTS#-PadP$2)") (class "Default")
      (node (ref "IC5") (pin "P$2") (pinfunction "RTS#_P$2") (pintype "bidirectional"))
    )
    (net (code "76") (name "unconnected-(USB1B-USBID-PadID)") (class "Default")
      (node (ref "USB1") (pin "ID") (pinfunction "USBID_ID") (pintype "bidirectional"))
    )
  )
)
